# 07_EL_CON.net
KiCad netlist of a schematic drawn in Altium Designer
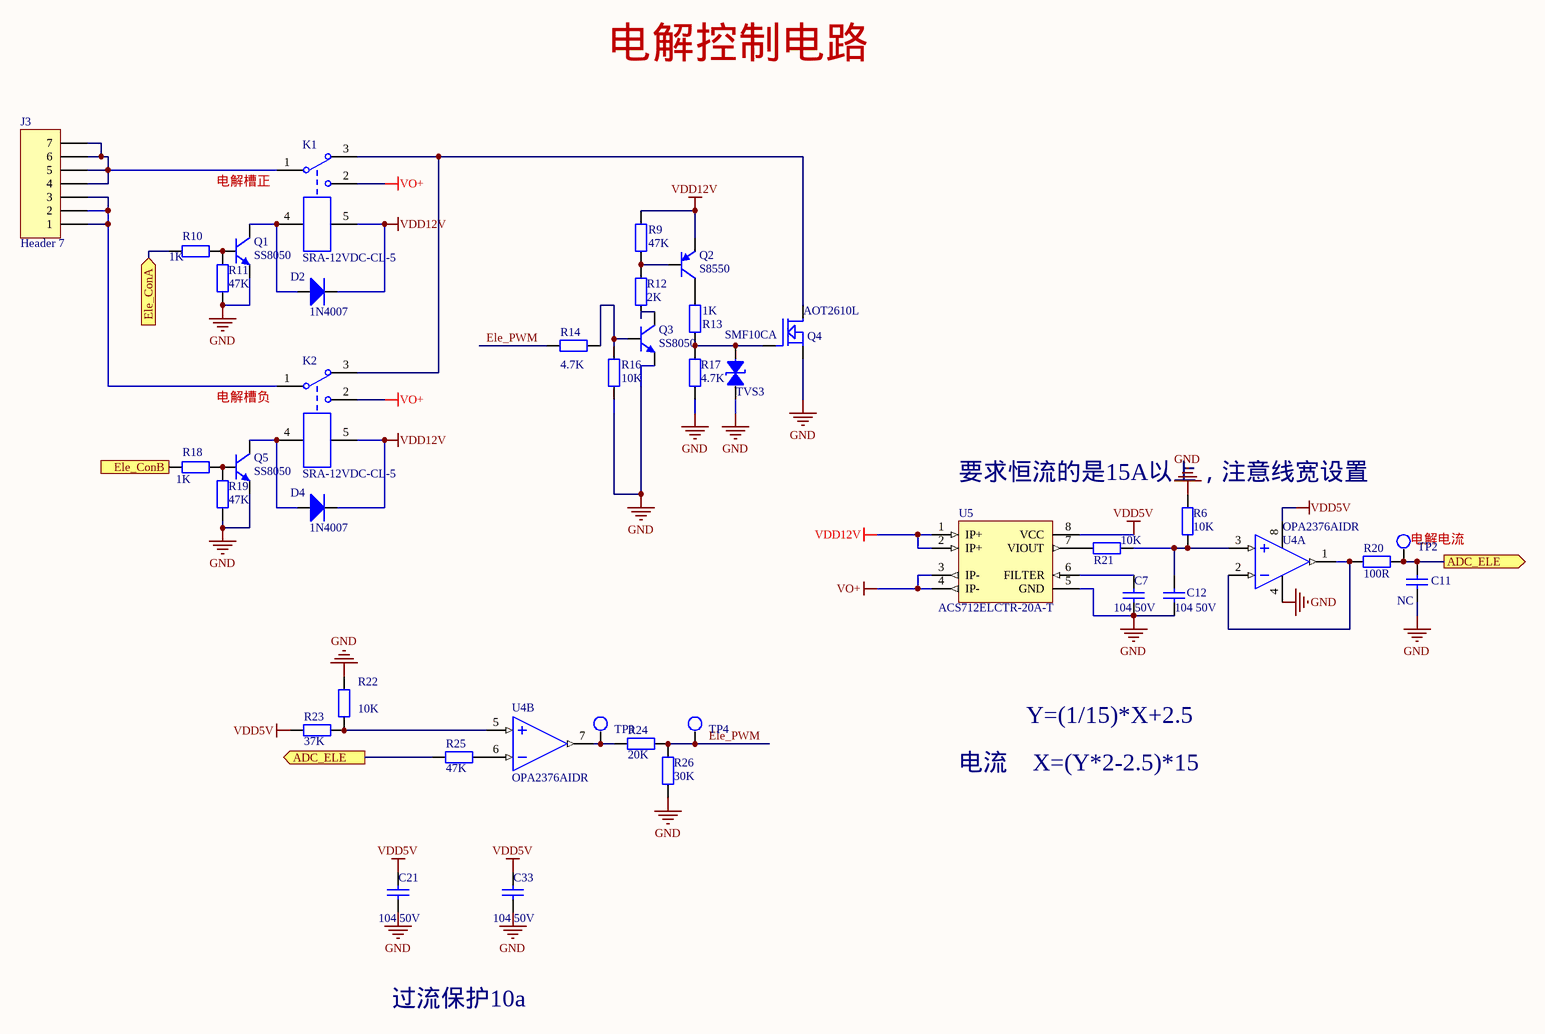
[diagram p0: 07_EL_CON.SchDoc]

(export (version "E")
  (design (tool "Eeschema 10.0.6"))
  (components
    (comp (ref "C7")
      (value "104 50V")
      (footprint "SMD-0603C")
      (description "贴片电容 10%")
      (libsource (lib "XiaoyI") (part "CAP4"))
    )
    (comp (ref "C11")
      (value "NC")
      (footprint "SMD-0603C")
      (description "贴片电容 10%")
      (libsource (lib "XiaoyI") (part "CAP4"))
    )
    (comp (ref "C12")
      (value "104 50V")
      (footprint "SMD-0603C")
      (description "贴片电容 10%")
      (libsource (lib "XiaoyI") (part "CAP4"))
    )
    (comp (ref "C21")
      (value "104 50V")
      (footprint "SMD-0603C")
      (description "贴片电容 20%")
      (libsource (lib "XiaoyI") (part "CAP4"))
    )
    (comp (ref "C33")
      (value "104 50V")
      (footprint "SMD-0603C")
      (description "贴片电容 20%")
      (libsource (lib "XiaoyI") (part "CAP4"))
    )
    (comp (ref "D2")
      (value "1N4007")
      (footprint "DO-214-AC")
      (description "贴片二极管")
      (libsource (lib "XiaoyI") (part "DIODE2"))
    )
    (comp (ref "D4")
      (value "1N4007")
      (footprint "DO-214-AC")
      (description "贴片二极管")
      (libsource (lib "XiaoyI") (part "DIODE2"))
    )
    (comp (ref "J3")
      (value "Header 7")
      (footprint "VH-AW-3.96*7P")
      (description "Header, 7-Pin")
      (fields (field (name "PUBLISHER") "Altium Limited"))
      (libsource (lib "Miscellaneous Connectors") (part "Header 7"))
    )
    (comp (ref "K1")
      (value "SRA-12VDC-CL-5")
      (footprint "SRA- 12V")
      (description "5V 继电器")
      (libsource (lib "XiaoyI") (part "JDQ1"))
    )
    (comp (ref "K2")
      (value "SRA-12VDC-CL-5")
      (footprint "SRA- 12V")
      (description "5V 继电器")
      (libsource (lib "XiaoyI") (part "JDQ1"))
    )
    (comp (ref "Q1")
      (value "SS8050")
      (footprint "SOT-23")
      (description "三极管")
      (libsource (lib "XiaoyI") (part "NPN-1"))
    )
    (comp (ref "Q2")
      (value "S8550")
      (footprint "SOT-23")
      (description "PNP")
      (libsource (lib "XiaoyI") (part "PNP"))
    )
    (comp (ref "Q3")
      (value "SS8050")
      (footprint "SOT-23")
      (description "三极管")
      (libsource (lib "XiaoyI") (part "NPN-1"))
    )
    (comp (ref "Q4")
      (value "AOT2610L")
      (footprint "Pcblib_20110825:to220")
      (libsource (lib "POWER") (part "SI7860"))
    )
    (comp (ref "Q5")
      (value "SS8050")
      (footprint "SOT-23")
      (description "三极管")
      (libsource (lib "XiaoyI") (part "NPN-1"))
    )
    (comp (ref "R6")
      (value "10K")
      (footprint "SMD-0603")
      (description "贴片电阻 1%")
      (libsource (lib "ABB") (part "RES0"))
    )
    (comp (ref "R9")
      (value "47K")
      (footprint "SMD-0603")
      (description "贴片电阻 5%")
      (libsource (lib "") (part "RES-SOP_1"))
    )
    (comp (ref "R10")
      (value "1K")
      (footprint "SMD-0603")
      (description "贴片电阻 5%")
      (libsource (lib "") (part "RES2_1"))
    )
    (comp (ref "R11")
      (value "47K")
      (footprint "SMD-0603")
      (description "贴片电阻 5%")
      (libsource (lib "XiaoyI") (part "RES2"))
    )
    (comp (ref "R12")
      (value "2K")
      (footprint "SMD-0603")
      (description "贴片电阻 5%")
      (libsource (lib "") (part "RES-SOP_2"))
    )
    (comp (ref "R13")
      (value "1K")
      (footprint "SMD-0603")
      (description "贴片电阻 5%")
      (libsource (lib "") (part "RES-SOP_1"))
    )
    (comp (ref "R14")
      (value "4.7K")
      (footprint "SMD-0603")
      (description "贴片电阻 5%")
      (libsource (lib "XiaoyI") (part "RES-SOP"))
    )
    (comp (ref "R16")
      (value "10K")
      (footprint "SMD-0603")
      (description "贴片电阻 5%")
      (libsource (lib "") (part "RES-SOP_1"))
    )
    (comp (ref "R17")
      (value "4.7K")
      (footprint "SMD-0603")
      (description "贴片电阻 5%")
      (libsource (lib "") (part "RES-SOP_2"))
    )
    (comp (ref "R18")
      (value "1K")
      (footprint "SMD-0603")
      (description "贴片电阻 5%")
      (libsource (lib "") (part "RES2_1"))
    )
    (comp (ref "R19")
      (value "47K")
      (footprint "SMD-0603")
      (description "贴片电阻 5%")
      (libsource (lib "XiaoyI") (part "RES2"))
    )
    (comp (ref "R20")
      (value "100R")
      (footprint "SMD-0603")
      (description "贴片电阻 5%")
      (libsource (lib "") (part "RES0_1"))
    )
    (comp (ref "R21")
      (value "10K")
      (footprint "SMD-0603")
      (description "贴片电阻 1%")
      (libsource (lib "") (part "RES0_1"))
    )
    (comp (ref "R22")
      (value "10K")
      (footprint "SMD-0603")
      (description "贴片电阻 5%")
      (libsource (lib "") (part "RES-SOP_1"))
    )
    (comp (ref "R23")
      (value "37K")
      (footprint "SMD-0603")
      (description "贴片电阻 5%")
      (libsource (lib "XiaoyI") (part "RES-SOP"))
    )
    (comp (ref "R24")
      (value "20K")
      (footprint "SMD-0603")
      (description "贴片电阻 5%")
      (libsource (lib "XiaoyI") (part "RES-SOP"))
    )
    (comp (ref "R25")
      (value "47K")
      (footprint "SMD-0603")
      (description "贴片电阻 5%")
      (libsource (lib "XiaoyI") (part "RES-SOP"))
    )
    (comp (ref "R26")
      (value "30K")
      (footprint "SMD-0603")
      (description "贴片电阻 5%")
      (libsource (lib "") (part "RES-SOP_2"))
    )
    (comp (ref "TP2") (value "TPS") (footprint "tpd") (libsource (lib "stm32") (part "TPS")))
    (comp (ref "TP3") (value "TPS") (footprint "tpd") (libsource (lib "stm32") (part "TPS")))
    (comp (ref "TP4") (value "TPS") (footprint "tpd") (libsource (lib "stm32") (part "TPS")))
    (comp (ref "TVS3")
      (value "SMF10CA")
      (footprint "SOD-123")
      (description "TVS 10V")
      (libsource (lib "XiaoyI") (part "TVS-1"))
    )
    (comp (ref "U4")
      (value "OPA2376AIDR")
      (footprint "SOIC-8")
      (description "运算放大器")
      (libsource (lib "XiaoyI") (part "LM358"))
    )
    (comp (ref "U5")
      (value "ACS712ELCTR-20A-T")
      (footprint "SO-8")
      (description "HALL 20A 电流传感器")
      (libsource (lib "XiaoyI") (part "ACS712"))
    )
  )
  (nets
    (net (code "1") (name "/ADC_ELE") (class "Default")
      (node (ref "C11") (pin "2") (pinfunction "2_2") (pintype "passive"))
      (node (ref "R20") (pin "1") (pinfunction "1_1") (pintype "passive"))
      (node (ref "R25") (pin "2") (pinfunction "2_2") (pintype "passive"))
      (node (ref "TP2") (pin "1") (pinfunction "1_1") (pintype "passive"))
    )
    (net (code "2") (name "/Ele_ConA") (class "Default")
      (node (ref "R10") (pin "1") (pinfunction "1_1") (pintype "passive"))
    )
    (net (code "3") (name "/Ele_ConB") (class "Default")
      (node (ref "R18") (pin "1") (pinfunction "1_1") (pintype "passive"))
    )
    (net (code "4") (name "/Ele_PWM") (class "Default")
      (node (ref "R14") (pin "2") (pinfunction "2_2") (pintype "passive"))
      (node (ref "R24") (pin "1") (pinfunction "1_1") (pintype "passive"))
      (node (ref "R26") (pin "1") (pinfunction "1_1") (pintype "passive"))
      (node (ref "TP4") (pin "1") (pinfunction "1_1") (pintype "passive"))
    )
    (net (code "5") (name "GND") (class "Default")
      (node (ref "C11") (pin "1") (pinfunction "1_1") (pintype "passive"))
      (node (ref "C12") (pin "2") (pinfunction "2_2") (pintype "passive"))
      (node (ref "C21") (pin "1") (pinfunction "1_1") (pintype "passive"))
      (node (ref "C33") (pin "1") (pinfunction "1_1") (pintype "passive"))
      (node (ref "C7") (pin "2") (pinfunction "2_2") (pintype "passive"))
      (node (ref "Q1") (pin "2") (pinfunction "E_2") (pintype "passive"))
      (node (ref "Q3") (pin "2") (pinfunction "E_2") (pintype "passive"))
      (node (ref "Q4") (pin "3") (pinfunction "S_3") (pintype "passive"))
      (node (ref "Q5") (pin "2") (pinfunction "E_2") (pintype "passive"))
      (node (ref "R11") (pin "1") (pinfunction "1_1") (pintype "passive"))
      (node (ref "R16") (pin "1") (pinfunction "1_1") (pintype "passive"))
      (node (ref "R17") (pin "2") (pinfunction "2_2") (pintype "passive"))
      (node (ref "R19") (pin "1") (pinfunction "1_1") (pintype "passive"))
      (node (ref "R22") (pin "2") (pinfunction "2_2") (pintype "passive"))
      (node (ref "R26") (pin "2") (pinfunction "2_2") (pintype "passive"))
      (node (ref "R6") (pin "1") (pinfunction "1_1") (pintype "passive"))
      (node (ref "TVS3") (pin "1") (pinfunction "A_1") (pintype "passive"))
      (node (ref "U4") (pin "4") (pinfunction "V-_4") (pintype "power_in"))
      (node (ref "U5") (pin "5") (pinfunction "GND_5") (pintype "power_in"))
    )
    (net (code "6") (name "Net-(D2-A)") (class "Default")
      (node (ref "D2") (pin "1") (pinfunction "A_1") (pintype "passive"))
      (node (ref "K1") (pin "4") (pinfunction "4_4") (pintype "passive"))
      (node (ref "Q1") (pin "3") (pinfunction "C_3") (pintype "passive"))
    )
    (net (code "7") (name "Net-(D4-A)") (class "Default")
      (node (ref "D4") (pin "1") (pinfunction "A_1") (pintype "passive"))
      (node (ref "K2") (pin "4") (pinfunction "4_4") (pintype "passive"))
      (node (ref "Q5") (pin "3") (pinfunction "C_3") (pintype "passive"))
    )
    (net (code "8") (name "Net-(J3-Pad1)") (class "Default")
      (node (ref "J3") (pin "1") (pinfunction "1_1") (pintype "passive"))
      (node (ref "J3") (pin "2") (pinfunction "2_2") (pintype "passive"))
      (node (ref "J3") (pin "3") (pinfunction "3_3") (pintype "passive"))
      (node (ref "K2") (pin "1") (pinfunction "1_1") (pintype "passive"))
    )
    (net (code "9") (name "Net-(J3-Pad4)") (class "Default")
      (node (ref "J3") (pin "4") (pinfunction "4_4") (pintype "passive"))
      (node (ref "J3") (pin "5") (pinfunction "5_5") (pintype "passive"))
      (node (ref "J3") (pin "6") (pinfunction "6_6") (pintype "passive"))
      (node (ref "J3") (pin "7") (pinfunction "7_7") (pintype "passive"))
      (node (ref "K1") (pin "1") (pinfunction "1_1") (pintype "passive"))
    )
    (net (code "10") (name "Net-(Q1-B)") (class "Default")
      (node (ref "Q1") (pin "1") (pinfunction "B_1") (pintype "passive"))
      (node (ref "R10") (pin "2") (pinfunction "2_2") (pintype "passive"))
      (node (ref "R11") (pin "2") (pinfunction "2_2") (pintype "passive"))
    )
    (net (code "11") (name "Net-(Q2-B)") (class "Default")
      (node (ref "Q2") (pin "1") (pinfunction "B_1") (pintype "passive"))
      (node (ref "R12") (pin "1") (pinfunction "1_1") (pintype "passive"))
      (node (ref "R9") (pin "1") (pinfunction "1_1") (pintype "passive"))
    )
    (net (code "12") (name "Net-(Q2-C)") (class "Default")
      (node (ref "Q2") (pin "3") (pinfunction "C_3") (pintype "passive"))
      (node (ref "R13") (pin "2") (pinfunction "2_2") (pintype "passive"))
    )
    (net (code "13") (name "Net-(Q3-B)") (class "Default")
      (node (ref "Q3") (pin "1") (pinfunction "B_1") (pintype "passive"))
      (node (ref "R14") (pin "1") (pinfunction "1_1") (pintype "passive"))
      (node (ref "R16") (pin "2") (pinfunction "2_2") (pintype "passive"))
    )
    (net (code "14") (name "Net-(Q3-C)") (class "Default")
      (node (ref "Q3") (pin "3") (pinfunction "C_3") (pintype "passive"))
      (node (ref "R12") (pin "2") (pinfunction "2_2") (pintype "passive"))
    )
    (net (code "15") (name "Net-(Q4-D)") (class "Default")
      (node (ref "K1") (pin "3") (pinfunction "3_3") (pintype "passive"))
      (node (ref "K2") (pin "3") (pinfunction "3_3") (pintype "passive"))
      (node (ref "Q4") (pin "2") (pinfunction "D_2") (pintype "passive"))
    )
    (net (code "16") (name "Net-(Q4-G)") (class "Default")
      (node (ref "Q4") (pin "1") (pinfunction "G_1") (pintype "passive"))
      (node (ref "R13") (pin "1") (pinfunction "1_1") (pintype "passive"))
      (node (ref "R17") (pin "1") (pinfunction "1_1") (pintype "passive"))
      (node (ref "TVS3") (pin "2") (pinfunction "B_2") (pintype "passive"))
    )
    (net (code "17") (name "Net-(Q5-B)") (class "Default")
      (node (ref "Q5") (pin "1") (pinfunction "B_1") (pintype "passive"))
      (node (ref "R18") (pin "2") (pinfunction "2_2") (pintype "passive"))
      (node (ref "R19") (pin "2") (pinfunction "2_2") (pintype "passive"))
    )
    (net (code "18") (name "Net-(U4A-IN1+)") (class "Default")
      (node (ref "C12") (pin "1") (pinfunction "1_1") (pintype "passive"))
      (node (ref "R21") (pin "1") (pinfunction "1_1") (pintype "passive"))
      (node (ref "R6") (pin "2") (pinfunction "2_2") (pintype "passive"))
      (node (ref "U4") (pin "3") (pinfunction "IN1+_3") (pintype "input"))
    )
    (net (code "19") (name "Net-(U4A-IN1-)") (class "Default")
      (node (ref "R20") (pin "2") (pinfunction "2_2") (pintype "passive"))
      (node (ref "U4") (pin "1") (pinfunction "OUT1_1") (pintype "output"))
      (node (ref "U4") (pin "2") (pinfunction "IN1-_2") (pintype "input"))
    )
    (net (code "20") (name "Net-(U4B-IN2+)") (class "Default")
      (node (ref "R22") (pin "1") (pinfunction "1_1") (pintype "passive"))
      (node (ref "R23") (pin "1") (pinfunction "1_1") (pintype "passive"))
      (node (ref "U4") (pin "5") (pinfunction "IN2+_5") (pintype "input"))
    )
    (net (code "21") (name "Net-(U4B-IN2-)") (class "Default")
      (node (ref "R25") (pin "1") (pinfunction "1_1") (pintype "passive"))
      (node (ref "U4") (pin "6") (pinfunction "IN2-_6") (pintype "input"))
    )
    (net (code "22") (name "Net-(U4B-OUT2)") (class "Default")
      (node (ref "R24") (pin "2") (pinfunction "2_2") (pintype "passive"))
      (node (ref "TP3") (pin "1") (pinfunction "1_1") (pintype "passive"))
      (node (ref "U4") (pin "7") (pinfunction "OUT2_7") (pintype "output"))
    )
    (net (code "23") (name "Net-(U5-FILTER)") (class "Default")
      (node (ref "C7") (pin "1") (pinfunction "1_1") (pintype "passive"))
      (node (ref "U5") (pin "6") (pinfunction "FILTER_6") (pintype "input"))
    )
    (net (code "24") (name "Net-(U5-VIOUT)") (class "Default")
      (node (ref "R21") (pin "2") (pinfunction "2_2") (pintype "passive"))
      (node (ref "U5") (pin "7") (pinfunction "VIOUT_7") (pintype "output"))
    )
    (net (code "25") (name "VDD5V") (class "Default")
      (node (ref "C21") (pin "2") (pinfunction "2_2") (pintype "passive"))
      (node (ref "C33") (pin "2") (pinfunction "2_2") (pintype "passive"))
      (node (ref "R23") (pin "2") (pinfunction "2_2") (pintype "passive"))
      (node (ref "U4") (pin "8") (pinfunction "V+_8") (pintype "power_in"))
      (node (ref "U5") (pin "8") (pinfunction "VCC_8") (pintype "power_in"))
    )
    (net (code "26") (name "VDD12V") (class "Default")
      (node (ref "D2") (pin "2") (pinfunction "K_2") (pintype "passive"))
      (node (ref "D4") (pin "2") (pinfunction "K_2") (pintype "passive"))
      (node (ref "K1") (pin "5") (pinfunction "5_5") (pintype "passive"))
      (node (ref "K2") (pin "5") (pinfunction "5_5") (pintype "passive"))
      (node (ref "Q2") (pin "2") (pinfunction "E_2") (pintype "passive"))
      (node (ref "R9") (pin "2") (pinfunction "2_2") (pintype "passive"))
      (node (ref "U5") (pin "1") (pinfunction "IP+_1") (pintype "input"))
      (node (ref "U5") (pin "2") (pinfunction "IP+_2") (pintype "input"))
    )
    (net (code "27") (name "VO+") (class "Default")
      (node (ref "K1") (pin "2") (pinfunction "2_2") (pintype "passive"))
      (node (ref "K2") (pin "2") (pinfunction "2_2") (pintype "passive"))
      (node (ref "U5") (pin "3") (pinfunction "IP-_3") (pintype "output"))
      (node (ref "U5") (pin "4") (pinfunction "IP-_4") (pintype "output"))
    )
  )
)
